# Mako_DSP_Pro_Power_R1_0.net
KiCad netlist of a schematic drawn in Altium Designer
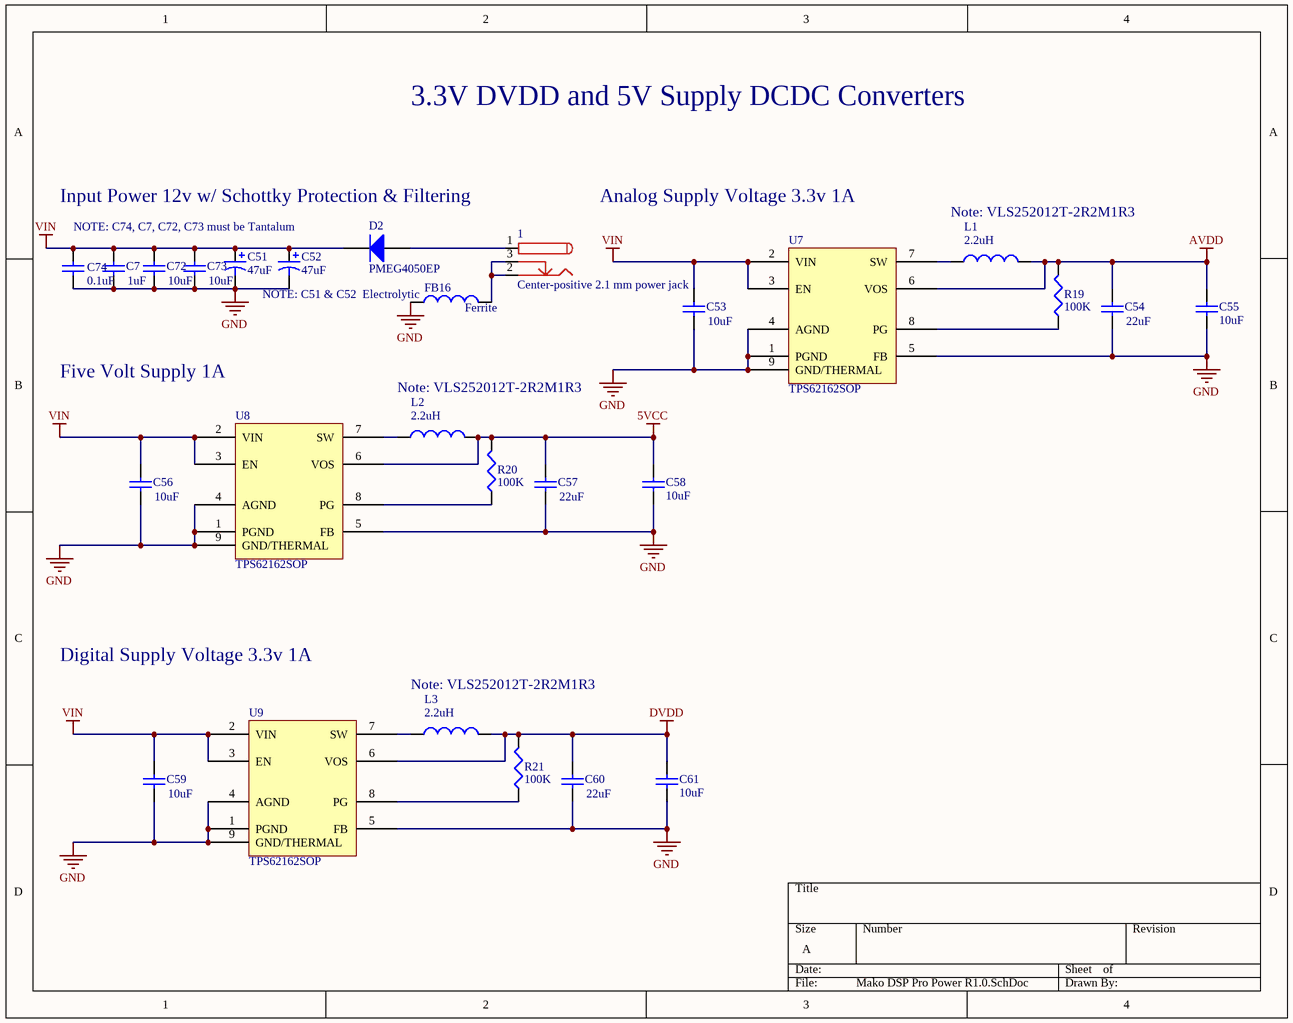
[diagram p0: Mako DSP Pro Power R1.0.SchDoc]

(export (version "E")
  (design (tool "Eeschema 10.0.6"))
  (components
    (comp (ref "1")
      (value "Center-positive 2.1 mm power jack")
      (footprint "PJ-102AH")
      (description "Power jack")
      (fields (field (name "PUBLISHER") "Altium Limited"))
      (libsource (lib "Rascal") (part "PWR2.5"))
    )
    (comp (ref "C7")
      (value "1uF")
      (footprint "C1206")
      (description "Capacitor (Semiconductor SIM Model)")
      (fields (field (name "Comment") "Cap Semi") (field (name "PUBLISHER") "Altium Limited"))
      (libsource (lib "Miscellaneous Devices") (part "Cap Semi"))
    )
    (comp (ref "C51")
      (value "47uF")
      (footprint "CAPPR2.5-6.3x5")
      (description "Polarized Capacitor (Radial)")
      (fields (field (name "Comment") "Cap Pol1") (field (name "PUBLISHER") "Altium Limited"))
      (libsource (lib "Miscellaneous Devices") (part "Cap Pol1"))
    )
    (comp (ref "C52")
      (value "47uF")
      (footprint "CAPPR2.5-6.3x5")
      (description "Polarized Capacitor (Radial)")
      (fields (field (name "Comment") "Cap Pol1") (field (name "PUBLISHER") "Altium Limited"))
      (libsource (lib "Miscellaneous Devices") (part "Cap Pol1"))
    )
    (comp (ref "C53")
      (value "10uF")
      (footprint "C1206")
      (description "Capacitor (Semiconductor SIM Model)")
      (fields (field (name "Comment") "Cap Semi") (field (name "PUBLISHER") "Altium Limited"))
      (libsource (lib "Miscellaneous Devices") (part "Cap Semi"))
    )
    (comp (ref "C54")
      (value "22uF")
      (footprint "C1206")
      (description "Capacitor (Semiconductor SIM Model)")
      (fields (field (name "Comment") "Cap Semi") (field (name "PUBLISHER") "Altium Limited"))
      (libsource (lib "Miscellaneous Devices") (part "Cap Semi"))
    )
    (comp (ref "C55")
      (value "10uF")
      (footprint "Panasonic VS B")
      (description "Capacitor (Semiconductor SIM Model)")
      (fields (field (name "Comment") "Cap Semi") (field (name "PUBLISHER") "Altium Limited"))
      (libsource (lib "Miscellaneous Devices") (part "Cap Semi"))
    )
    (comp (ref "C56")
      (value "10uF")
      (footprint "C1206")
      (description "Capacitor (Semiconductor SIM Model)")
      (fields (field (name "Comment") "Cap Semi") (field (name "PUBLISHER") "Altium Limited"))
      (libsource (lib "Miscellaneous Devices") (part "Cap Semi"))
    )
    (comp (ref "C57")
      (value "22uF")
      (footprint "C1206")
      (description "Capacitor (Semiconductor SIM Model)")
      (fields (field (name "Comment") "Cap Semi") (field (name "PUBLISHER") "Altium Limited"))
      (libsource (lib "Miscellaneous Devices") (part "Cap Semi"))
    )
    (comp (ref "C58")
      (value "10uF")
      (footprint "Panasonic VS B")
      (description "Capacitor (Semiconductor SIM Model)")
      (fields (field (name "Comment") "Cap Semi") (field (name "PUBLISHER") "Altium Limited"))
      (libsource (lib "Miscellaneous Devices") (part "Cap Semi"))
    )
    (comp (ref "C59")
      (value "10uF")
      (footprint "C1206")
      (description "Capacitor (Semiconductor SIM Model)")
      (fields (field (name "Comment") "Cap Semi") (field (name "PUBLISHER") "Altium Limited"))
      (libsource (lib "Miscellaneous Devices") (part "Cap Semi"))
    )
    (comp (ref "C60")
      (value "22uF")
      (footprint "C1206")
      (description "Capacitor (Semiconductor SIM Model)")
      (fields (field (name "Comment") "Cap Semi") (field (name "PUBLISHER") "Altium Limited"))
      (libsource (lib "Miscellaneous Devices") (part "Cap Semi"))
    )
    (comp (ref "C61")
      (value "10uF")
      (footprint "Panasonic VS B")
      (description "Capacitor (Semiconductor SIM Model)")
      (fields (field (name "Comment") "Cap Semi") (field (name "PUBLISHER") "Altium Limited"))
      (libsource (lib "Miscellaneous Devices") (part "Cap Semi"))
    )
    (comp (ref "C72")
      (value "10uF")
      (footprint "C1206")
      (description "Capacitor (Semiconductor SIM Model)")
      (fields (field (name "Comment") "Cap Semi") (field (name "PUBLISHER") "Altium Limited"))
      (libsource (lib "Miscellaneous Devices") (part "Cap Semi"))
    )
    (comp (ref "C73")
      (value "10uF")
      (footprint "C1206")
      (description "Capacitor (Semiconductor SIM Model)")
      (fields (field (name "Comment") "Cap Semi") (field (name "PUBLISHER") "Altium Limited"))
      (libsource (lib "Miscellaneous Devices") (part "Cap Semi"))
    )
    (comp (ref "C74")
      (value "0.1uF")
      (footprint "C1206")
      (description "Capacitor (Semiconductor SIM Model)")
      (fields (field (name "Comment") "Cap Semi") (field (name "PUBLISHER") "Altium Limited"))
      (libsource (lib "Miscellaneous Devices") (part "Cap Semi"))
    )
    (comp (ref "D2")
      (value "PMEG4050EP")
      (footprint "PMEG4050EP")
      (description "Default Diode")
      (fields (field (name "PUBLISHER") "Altium Limited"))
      (libsource (lib "Miscellaneous Devices") (part "Diode"))
    )
    (comp (ref "FB16")
      (value "Ferrite")
      (footprint "SM 0805 - gap trimmed")
      (description "Inductor")
      (fields (field (name "PUBLISHER") "Altium Limited"))
      (libsource (lib "Miscellaneous Devices") (part "Inductor"))
    )
    (comp (ref "L1")
      (value "2.2uH")
      (footprint "VLS252012T-2R2M1R3")
      (description "Inductor")
      (fields (field (name "PUBLISHER") "Altium Limited"))
      (libsource (lib "Miscellaneous Devices") (part "Inductor"))
    )
    (comp (ref "L2")
      (value "2.2uH")
      (footprint "VLS252012T-2R2M1R3")
      (description "Inductor")
      (fields (field (name "PUBLISHER") "Altium Limited"))
      (libsource (lib "Miscellaneous Devices") (part "Inductor"))
    )
    (comp (ref "L3")
      (value "2.2uH")
      (footprint "VLS252012T-2R2M1R3")
      (description "Inductor")
      (fields (field (name "PUBLISHER") "Altium Limited"))
      (libsource (lib "Miscellaneous Devices") (part "Inductor"))
    )
    (comp (ref "R19")
      (value "100K")
      (footprint "RESC2012L")
      (description "Resistor")
      (fields (field (name "Comment") "Res3") (field (name "PUBLISHER") "Altium Limited"))
      (libsource (lib "Miscellaneous Devices") (part "Res3"))
    )
    (comp (ref "R20")
      (value "100K")
      (footprint "RESC2012L")
      (description "Resistor")
      (fields (field (name "Comment") "Res3") (field (name "PUBLISHER") "Altium Limited"))
      (libsource (lib "Miscellaneous Devices") (part "Res3"))
    )
    (comp (ref "R21")
      (value "100K")
      (footprint "RESC2012L")
      (description "Resistor")
      (fields (field (name "Comment") "Res3") (field (name "PUBLISHER") "Altium Limited"))
      (libsource (lib "Miscellaneous Devices") (part "Res3"))
    )
    (comp (ref "U7")
      (value "TPS62162SOP")
      (footprint "TPS62162SOP")
      (libsource (lib "Adams Altium Library") (part "TPS62162SOP"))
    )
    (comp (ref "U8")
      (value "TPS62162SOP")
      (footprint "TPS62162SOP")
      (libsource (lib "Adams Altium Library") (part "TPS62162SOP"))
    )
    (comp (ref "U9")
      (value "TPS62162SOP")
      (footprint "TPS62162SOP")
      (libsource (lib "Adams Altium Library") (part "TPS62162SOP"))
    )
  )
  (nets
    (net (code "1") (name "5VCC") (class "Default")
      (node (ref "C57") (pin "2") (pinfunction "2_2") (pintype "passive"))
      (node (ref "C58") (pin "1") (pinfunction "1_1") (pintype "passive"))
      (node (ref "L2") (pin "2") (pinfunction "2_2") (pintype "passive"))
      (node (ref "R20") (pin "2") (pinfunction "2_2") (pintype "passive"))
      (node (ref "U8") (pin "6") (pinfunction "VOS_6") (pintype "passive"))
    )
    (net (code "2") (name "AVDD") (class "Default")
      (node (ref "C54") (pin "2") (pinfunction "2_2") (pintype "passive"))
      (node (ref "C55") (pin "1") (pinfunction "1_1") (pintype "passive"))
      (node (ref "L1") (pin "2") (pinfunction "2_2") (pintype "passive"))
      (node (ref "R19") (pin "2") (pinfunction "2_2") (pintype "passive"))
      (node (ref "U7") (pin "6") (pinfunction "VOS_6") (pintype "passive"))
    )
    (net (code "3") (name "DVDD") (class "Default")
      (node (ref "C60") (pin "2") (pinfunction "2_2") (pintype "passive"))
      (node (ref "C61") (pin "1") (pinfunction "1_1") (pintype "passive"))
      (node (ref "L3") (pin "2") (pinfunction "2_2") (pintype "passive"))
      (node (ref "R21") (pin "2") (pinfunction "2_2") (pintype "passive"))
      (node (ref "U9") (pin "6") (pinfunction "VOS_6") (pintype "passive"))
    )
    (net (code "4") (name "GND") (class "Default")
      (node (ref "C51") (pin "2") (pinfunction "2_2") (pintype "passive"))
      (node (ref "C52") (pin "2") (pinfunction "2_2") (pintype "passive"))
      (node (ref "C53") (pin "1") (pinfunction "1_1") (pintype "passive"))
      (node (ref "C54") (pin "1") (pinfunction "1_1") (pintype "passive"))
      (node (ref "C55") (pin "2") (pinfunction "2_2") (pintype "passive"))
      (node (ref "C56") (pin "1") (pinfunction "1_1") (pintype "passive"))
      (node (ref "C57") (pin "1") (pinfunction "1_1") (pintype "passive"))
      (node (ref "C58") (pin "2") (pinfunction "2_2") (pintype "passive"))
      (node (ref "C59") (pin "1") (pinfunction "1_1") (pintype "passive"))
      (node (ref "C60") (pin "1") (pinfunction "1_1") (pintype "passive"))
      (node (ref "C61") (pin "2") (pinfunction "2_2") (pintype "passive"))
      (node (ref "C7") (pin "1") (pinfunction "1_1") (pintype "passive"))
      (node (ref "C72") (pin "1") (pinfunction "1_1") (pintype "passive"))
      (node (ref "C73") (pin "1") (pinfunction "1_1") (pintype "passive"))
      (node (ref "C74") (pin "1") (pinfunction "1_1") (pintype "passive"))
      (node (ref "FB16") (pin "1") (pinfunction "1_1") (pintype "passive"))
      (node (ref "U7") (pin "1") (pinfunction "PGND_1") (pintype "passive"))
      (node (ref "U7") (pin "4") (pinfunction "AGND_4") (pintype "passive"))
      (node (ref "U7") (pin "5") (pinfunction "FB_5") (pintype "passive"))
      (node (ref "U7") (pin "9") (pinfunction "GND/THERMAL_9") (pintype "passive"))
      (node (ref "U8") (pin "1") (pinfunction "PGND_1") (pintype "passive"))
      (node (ref "U8") (pin "4") (pinfunction "AGND_4") (pintype "passive"))
      (node (ref "U8") (pin "5") (pinfunction "FB_5") (pintype "passive"))
      (node (ref "U8") (pin "9") (pinfunction "GND/THERMAL_9") (pintype "passive"))
      (node (ref "U9") (pin "1") (pinfunction "PGND_1") (pintype "passive"))
      (node (ref "U9") (pin "4") (pinfunction "AGND_4") (pintype "passive"))
      (node (ref "U9") (pin "5") (pinfunction "FB_5") (pintype "passive"))
      (node (ref "U9") (pin "9") (pinfunction "GND/THERMAL_9") (pintype "passive"))
    )
    (net (code "5") (name "Net-(1-Pad2)") (class "Default")
      (node (ref "1") (pin "2") (pinfunction "2_2") (pintype "power_in"))
      (node (ref "1") (pin "3") (pinfunction "3_3") (pintype "power_in"))
      (node (ref "FB16") (pin "2") (pinfunction "2_2") (pintype "passive"))
    )
    (net (code "6") (name "Net-(D2-K)") (class "Default")
      (node (ref "1") (pin "1") (pinfunction "1_1") (pintype "power_in"))
      (node (ref "D2") (pin "2") (pinfunction "K_2") (pintype "passive"))
    )
    (net (code "7") (name "Net-(U7-PG)") (class "Default")
      (node (ref "R19") (pin "1") (pinfunction "1_1") (pintype "passive"))
      (node (ref "U7") (pin "8") (pinfunction "PG_8") (pintype "passive"))
    )
    (net (code "8") (name "Net-(U7-SW)") (class "Default")
      (node (ref "L1") (pin "1") (pinfunction "1_1") (pintype "passive"))
      (node (ref "U7") (pin "7") (pinfunction "SW_7") (pintype "passive"))
    )
    (net (code "9") (name "Net-(U8-PG)") (class "Default")
      (node (ref "R20") (pin "1") (pinfunction "1_1") (pintype "passive"))
      (node (ref "U8") (pin "8") (pinfunction "PG_8") (pintype "passive"))
    )
    (net (code "10") (name "Net-(U8-SW)") (class "Default")
      (node (ref "L2") (pin "1") (pinfunction "1_1") (pintype "passive"))
      (node (ref "U8") (pin "7") (pinfunction "SW_7") (pintype "passive"))
    )
    (net (code "11") (name "Net-(U9-PG)") (class "Default")
      (node (ref "R21") (pin "1") (pinfunction "1_1") (pintype "passive"))
      (node (ref "U9") (pin "8") (pinfunction "PG_8") (pintype "passive"))
    )
    (net (code "12") (name "Net-(U9-SW)") (class "Default")
      (node (ref "L3") (pin "1") (pinfunction "1_1") (pintype "passive"))
      (node (ref "U9") (pin "7") (pinfunction "SW_7") (pintype "passive"))
    )
    (net (code "13") (name "VIN") (class "Default")
      (node (ref "C51") (pin "1") (pinfunction "1_1") (pintype "passive"))
      (node (ref "C52") (pin "1") (pinfunction "1_1") (pintype "passive"))
      (node (ref "C53") (pin "2") (pinfunction "2_2") (pintype "passive"))
      (node (ref "C56") (pin "2") (pinfunction "2_2") (pintype "passive"))
      (node (ref "C59") (pin "2") (pinfunction "2_2") (pintype "passive"))
      (node (ref "C7") (pin "2") (pinfunction "2_2") (pintype "passive"))
      (node (ref "C72") (pin "2") (pinfunction "2_2") (pintype "passive"))
      (node (ref "C73") (pin "2") (pinfunction "2_2") (pintype "passive"))
      (node (ref "C74") (pin "2") (pinfunction "2_2") (pintype "passive"))
      (node (ref "D2") (pin "1") (pinfunction "A_1") (pintype "passive"))
      (node (ref "U7") (pin "2") (pinfunction "VIN_2") (pintype "passive"))
      (node (ref "U7") (pin "3") (pinfunction "EN_3") (pintype "passive"))
      (node (ref "U8") (pin "2") (pinfunction "VIN_2") (pintype "passive"))
      (node (ref "U8") (pin "3") (pinfunction "EN_3") (pintype "passive"))
      (node (ref "U9") (pin "2") (pinfunction "VIN_2") (pintype "passive"))
      (node (ref "U9") (pin "3") (pinfunction "EN_3") (pintype "passive"))
    )
  )
)
